# CE_BJTInfineonSOT343_v1.net
KiCad netlist of a schematic drawn in Altium Designer
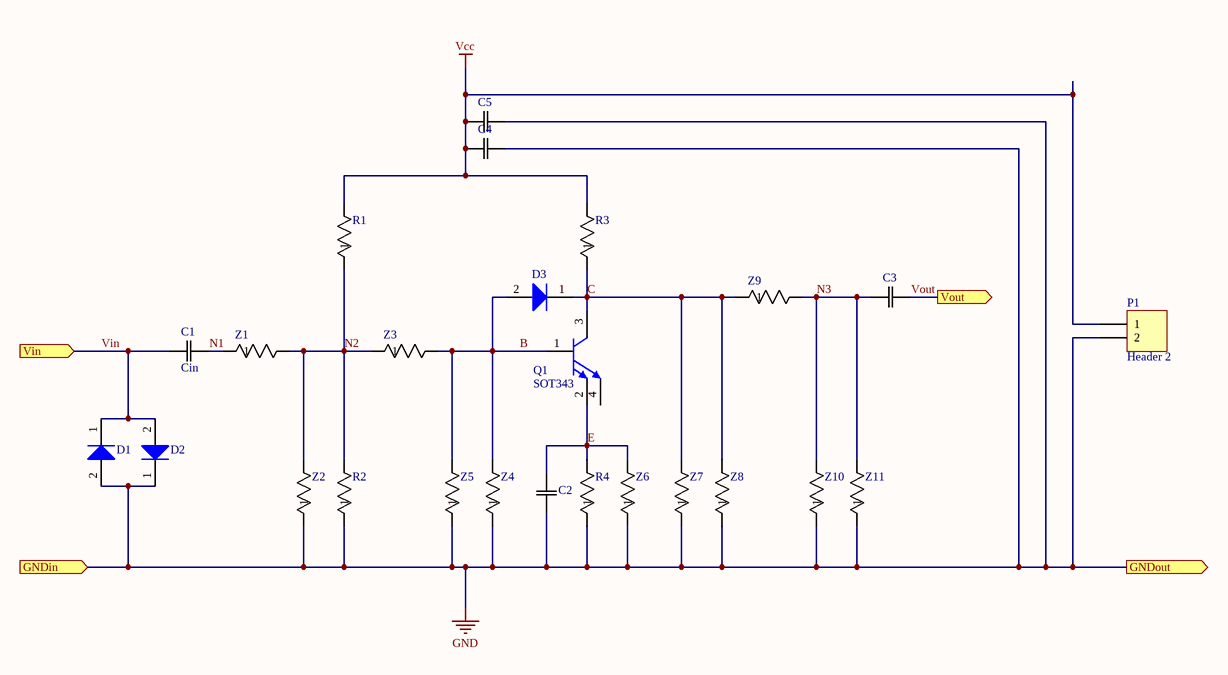
[diagram p0: CE_BJTInfineonSOT343_v1.SchDoc]

(export (version "E")
  (design (tool "Eeschema 10.0.6"))
  (components
    (comp (ref "C1")
      (value "Cin")
      (footprint "C0201")
      (description "No Description Available")
      (fields
        (field (name "MANUFACTURER_PART_NUMBER") "C0201C270J3GACTU")
        (field (name "COPYRIGHT") "Copyright (C) 2018 Accelerated Designs. All rights reserved")
      )
      (libsource (lib "0201Capacitor_Yageo") (part "C0201C270J3GACTU"))
    )
    (comp (ref "C2")
      (value "~")
      (footprint "C0201")
      (description "No Description Available")
      (fields
        (field (name "MANUFACTURER_PART_NUMBER") "C0201C270J3GACTU")
        (field (name "COPYRIGHT") "Copyright (C) 2018 Accelerated Designs. All rights reserved")
      )
      (libsource (lib "0201Capacitor_Yageo") (part "C0201C270J3GACTU"))
    )
    (comp (ref "C3")
      (value "~")
      (footprint "C0201")
      (description "No Description Available")
      (fields
        (field (name "MANUFACTURER_PART_NUMBER") "C0201C270J3GACTU")
        (field (name "COPYRIGHT") "Copyright (C) 2018 Accelerated Designs. All rights reserved")
      )
      (libsource (lib "0201Capacitor_Yageo") (part "C0201C270J3GACTU"))
    )
    (comp (ref "C4")
      (value "~")
      (footprint "CAP_CBR_0201")
      (description "No Description Available")
      (fields
        (field (name "MANUFACTURER_PART_NUMBER") "CBR02C399C3GAC")
        (field (name "COPYRIGHT") "Copyright (C) 2018 Accelerated Designs. All rights reserved")
      )
      (libsource (lib "0201Capacitor_KEMET") (part "CBR02C399C3GAC"))
    )
    (comp (ref "C5")
      (value "~")
      (footprint "CAP_CBR_0201")
      (description "No Description Available")
      (fields
        (field (name "MANUFACTURER_PART_NUMBER") "CBR02C399C3GAC")
        (field (name "COPYRIGHT") "Copyright (C) 2018 Accelerated Designs. All rights reserved")
      )
      (libsource (lib "0201Capacitor_KEMET") (part "CBR02C399C3GAC"))
    )
    (comp (ref "D1")
      (value "~")
      (footprint "INF-SOD323_V")
      (description "Single Silicon Schottky Diode, 110 mA IF Max, SOD32, Green")
      (fields (field (name "MANUFACTURER") "Infineon") (field (name "PARTNUMBER") "BAT15-03W"))
      (libsource (lib "Infineon_RFSchottkyDiode_SOD323") (part "BAT15-03W"))
    )
    (comp (ref "D2")
      (value "~")
      (footprint "INF-SOD323_V")
      (description "Single Silicon Schottky Diode, 110 mA IF Max, SOD32, Green")
      (fields (field (name "MANUFACTURER") "Infineon") (field (name "PARTNUMBER") "BAT15-03W"))
      (libsource (lib "Infineon_RFSchottkyDiode_SOD323") (part "BAT15-03W"))
    )
    (comp (ref "D3")
      (value "~")
      (footprint "INF-SOD323_V")
      (description "Single Silicon Schottky Diode, 110 mA IF Max, SOD32, Green")
      (fields (field (name "MANUFACTURER") "Infineon") (field (name "PARTNUMBER") "BAT15-03W"))
      (libsource (lib "Infineon_RFSchottkyDiode_SOD323") (part "BAT15-03W"))
    )
    (comp (ref "P1")
      (value "Header 2")
      (footprint "HDR1X2")
      (description "Header, 2-Pin")
      (fields (field (name "PUBLISHER") "Altium Limited"))
      (libsource (lib "Miscellaneous Connectors") (part "Header 2"))
    )
    (comp (ref "Q1")
      (value "SOT343")
      (footprint "INF-SOT343_V")
      (fields (field (name "MANUFACTURER") "Infineon") (field (name "PARTNUMBER") "BFP840ESD"))
      (libsource (lib "Infineon_RFBJT_SOT343") (part "BFP840ESD"))
    )
    (comp (ref "R1")
      (value "~")
      (footprint "RES_RC0201_P6XP3")
      (description "No Description Available")
      (fields
        (field (name "MANUFACTURER_PART_NUMBER") "RC0201FR-0718KL")
        (field (name "COPYRIGHT") "Copyright (C) 2018 Accelerated Designs. All rights reserved")
      )
      (libsource (lib "0201Resistor_Yageo") (part "RC0201FR-0718KL"))
    )
    (comp (ref "R2")
      (value "~")
      (footprint "RES_RC0201_P6XP3")
      (description "No Description Available")
      (fields
        (field (name "MANUFACTURER_PART_NUMBER") "RC0201FR-0718KL")
        (field (name "COPYRIGHT") "Copyright (C) 2018 Accelerated Designs. All rights reserved")
      )
      (libsource (lib "0201Resistor_Yageo") (part "RC0201FR-0718KL"))
    )
    (comp (ref "R3")
      (value "~")
      (footprint "RES_RC0201_P6XP3")
      (description "No Description Available")
      (fields
        (field (name "MANUFACTURER_PART_NUMBER") "RC0201FR-0718KL")
        (field (name "COPYRIGHT") "Copyright (C) 2018 Accelerated Designs. All rights reserved")
      )
      (libsource (lib "0201Resistor_Yageo") (part "RC0201FR-0718KL"))
    )
    (comp (ref "R4")
      (value "~")
      (footprint "RES_RC0201_P6XP3")
      (description "No Description Available")
      (fields
        (field (name "MANUFACTURER_PART_NUMBER") "RC0201FR-0718KL")
        (field (name "COPYRIGHT") "Copyright (C) 2018 Accelerated Designs. All rights reserved")
      )
      (libsource (lib "0201Resistor_Yageo") (part "RC0201FR-0718KL"))
    )
    (comp (ref "Z1")
      (value "~")
      (footprint "RES_RC0201_P6XP3")
      (description "No Description Available")
      (fields
        (field (name "MANUFACTURER_PART_NUMBER") "RC0201FR-0718KL")
        (field (name "COPYRIGHT") "Copyright (C) 2018 Accelerated Designs. All rights reserved")
      )
      (libsource (lib "0201Resistor_Yageo") (part "RC0201FR-0718KL"))
    )
    (comp (ref "Z2")
      (value "~")
      (footprint "RES_RC0201_P6XP3")
      (description "No Description Available")
      (fields
        (field (name "MANUFACTURER_PART_NUMBER") "RC0201FR-0718KL")
        (field (name "COPYRIGHT") "Copyright (C) 2018 Accelerated Designs. All rights reserved")
      )
      (libsource (lib "0201Resistor_Yageo") (part "RC0201FR-0718KL"))
    )
    (comp (ref "Z3")
      (value "~")
      (footprint "RES_RC0201_P6XP3")
      (description "No Description Available")
      (fields
        (field (name "MANUFACTURER_PART_NUMBER") "RC0201FR-0718KL")
        (field (name "COPYRIGHT") "Copyright (C) 2018 Accelerated Designs. All rights reserved")
      )
      (libsource (lib "0201Resistor_Yageo") (part "RC0201FR-0718KL"))
    )
    (comp (ref "Z4")
      (value "~")
      (footprint "RES_RC0201_P6XP3")
      (description "No Description Available")
      (fields
        (field (name "MANUFACTURER_PART_NUMBER") "RC0201FR-0718KL")
        (field (name "COPYRIGHT") "Copyright (C) 2018 Accelerated Designs. All rights reserved")
      )
      (libsource (lib "0201Resistor_Yageo") (part "RC0201FR-0718KL"))
    )
    (comp (ref "Z5")
      (value "~")
      (footprint "RES_RC0201_P6XP3")
      (description "No Description Available")
      (fields
        (field (name "MANUFACTURER_PART_NUMBER") "RC0201FR-0718KL")
        (field (name "COPYRIGHT") "Copyright (C) 2018 Accelerated Designs. All rights reserved")
      )
      (libsource (lib "0201Resistor_Yageo") (part "RC0201FR-0718KL"))
    )
    (comp (ref "Z6")
      (value "~")
      (footprint "RES_RC0201_P6XP3")
      (description "No Description Available")
      (fields
        (field (name "MANUFACTURER_PART_NUMBER") "RC0201FR-0718KL")
        (field (name "COPYRIGHT") "Copyright (C) 2018 Accelerated Designs. All rights reserved")
      )
      (libsource (lib "0201Resistor_Yageo") (part "RC0201FR-0718KL"))
    )
    (comp (ref "Z7")
      (value "~")
      (footprint "RES_RC0201_P6XP3")
      (description "No Description Available")
      (fields
        (field (name "MANUFACTURER_PART_NUMBER") "RC0201FR-0718KL")
        (field (name "COPYRIGHT") "Copyright (C) 2018 Accelerated Designs. All rights reserved")
      )
      (libsource (lib "0201Resistor_Yageo") (part "RC0201FR-0718KL"))
    )
    (comp (ref "Z8")
      (value "~")
      (footprint "RES_RC0201_P6XP3")
      (description "No Description Available")
      (fields
        (field (name "MANUFACTURER_PART_NUMBER") "RC0201FR-0718KL")
        (field (name "COPYRIGHT") "Copyright (C) 2018 Accelerated Designs. All rights reserved")
      )
      (libsource (lib "0201Resistor_Yageo") (part "RC0201FR-0718KL"))
    )
    (comp (ref "Z9")
      (value "~")
      (footprint "RES_RC0201_P6XP3")
      (description "No Description Available")
      (fields
        (field (name "MANUFACTURER_PART_NUMBER") "RC0201FR-0718KL")
        (field (name "COPYRIGHT") "Copyright (C) 2018 Accelerated Designs. All rights reserved")
      )
      (libsource (lib "0201Resistor_Yageo") (part "RC0201FR-0718KL"))
    )
    (comp (ref "Z10")
      (value "~")
      (footprint "RES_RC0201_P6XP3")
      (description "No Description Available")
      (fields
        (field (name "MANUFACTURER_PART_NUMBER") "RC0201FR-0718KL")
        (field (name "COPYRIGHT") "Copyright (C) 2018 Accelerated Designs. All rights reserved")
      )
      (libsource (lib "0201Resistor_Yageo") (part "RC0201FR-0718KL"))
    )
    (comp (ref "Z11")
      (value "~")
      (footprint "RES_RC0201_P6XP3")
      (description "No Description Available")
      (fields
        (field (name "MANUFACTURER_PART_NUMBER") "RC0201FR-0718KL")
        (field (name "COPYRIGHT") "Copyright (C) 2018 Accelerated Designs. All rights reserved")
      )
      (libsource (lib "0201Resistor_Yageo") (part "RC0201FR-0718KL"))
    )
  )
  (nets
    (net (code "1") (name "/B") (class "Default")
      (node (ref "D3") (pin "2") (pinfunction "A_2") (pintype "passive"))
      (node (ref "Q1") (pin "1") (pinfunction "B_1") (pintype "passive"))
      (node (ref "Z3") (pin "2") (pinfunction "2_2") (pintype "passive"))
      (node (ref "Z4") (pin "2") (pinfunction "2_2") (pintype "passive"))
      (node (ref "Z5") (pin "2") (pinfunction "2_2") (pintype "passive"))
    )
    (net (code "2") (name "/C") (class "Default")
      (node (ref "D3") (pin "1") (pinfunction "K_1") (pintype "passive"))
      (node (ref "Q1") (pin "3") (pinfunction "C_3") (pintype "passive"))
      (node (ref "R3") (pin "1") (pinfunction "1_1") (pintype "passive"))
      (node (ref "Z7") (pin "2") (pinfunction "2_2") (pintype "passive"))
      (node (ref "Z8") (pin "2") (pinfunction "2_2") (pintype "passive"))
      (node (ref "Z9") (pin "1") (pinfunction "1_1") (pintype "passive"))
    )
    (net (code "3") (name "/E") (class "Default")
      (node (ref "C2") (pin "2") (pinfunction "2_2") (pintype "passive"))
      (node (ref "Q1") (pin "2") (pinfunction "E_2") (pintype "passive"))
      (node (ref "R4") (pin "2") (pinfunction "2_2") (pintype "passive"))
      (node (ref "Z6") (pin "2") (pinfunction "2_2") (pintype "passive"))
    )
    (net (code "4") (name "/N1") (class "Default")
      (node (ref "C1") (pin "2") (pinfunction "2_2") (pintype "passive"))
      (node (ref "Z1") (pin "1") (pinfunction "1_1") (pintype "passive"))
    )
    (net (code "5") (name "/N2") (class "Default")
      (node (ref "R1") (pin "1") (pinfunction "1_1") (pintype "passive"))
      (node (ref "R2") (pin "2") (pinfunction "2_2") (pintype "passive"))
      (node (ref "Z1") (pin "2") (pinfunction "2_2") (pintype "passive"))
      (node (ref "Z2") (pin "2") (pinfunction "2_2") (pintype "passive"))
      (node (ref "Z3") (pin "1") (pinfunction "1_1") (pintype "passive"))
    )
    (net (code "6") (name "/N3") (class "Default")
      (node (ref "C3") (pin "1") (pinfunction "1_1") (pintype "passive"))
      (node (ref "Z10") (pin "2") (pinfunction "2_2") (pintype "passive"))
      (node (ref "Z11") (pin "2") (pinfunction "2_2") (pintype "passive"))
      (node (ref "Z9") (pin "2") (pinfunction "2_2") (pintype "passive"))
    )
    (net (code "7") (name "/Vin") (class "Default")
      (node (ref "C1") (pin "1") (pinfunction "1_1") (pintype "passive"))
      (node (ref "D1") (pin "1") (pinfunction "K_1") (pintype "passive"))
      (node (ref "D2") (pin "2") (pinfunction "A_2") (pintype "passive"))
    )
    (net (code "8") (name "/Vout") (class "Default")
      (node (ref "C3") (pin "2") (pinfunction "2_2") (pintype "passive"))
    )
    (net (code "9") (name "GND") (class "Default")
      (node (ref "C2") (pin "1") (pinfunction "1_1") (pintype "passive"))
      (node (ref "C4") (pin "2") (pinfunction "2_2") (pintype "passive"))
      (node (ref "C5") (pin "2") (pinfunction "2_2") (pintype "passive"))
      (node (ref "D1") (pin "2") (pinfunction "A_2") (pintype "passive"))
      (node (ref "D2") (pin "1") (pinfunction "K_1") (pintype "passive"))
      (node (ref "P1") (pin "2") (pinfunction "2_2") (pintype "passive"))
      (node (ref "R2") (pin "1") (pinfunction "1_1") (pintype "passive"))
      (node (ref "R4") (pin "1") (pinfunction "1_1") (pintype "passive"))
      (node (ref "Z10") (pin "1") (pinfunction "1_1") (pintype "passive"))
      (node (ref "Z11") (pin "1") (pinfunction "1_1") (pintype "passive"))
      (node (ref "Z2") (pin "1") (pinfunction "1_1") (pintype "passive"))
      (node (ref "Z4") (pin "1") (pinfunction "1_1") (pintype "passive"))
      (node (ref "Z5") (pin "1") (pinfunction "1_1") (pintype "passive"))
      (node (ref "Z6") (pin "1") (pinfunction "1_1") (pintype "passive"))
      (node (ref "Z7") (pin "1") (pinfunction "1_1") (pintype "passive"))
      (node (ref "Z8") (pin "1") (pinfunction "1_1") (pintype "passive"))
    )
    (net (code "10") (name "Vcc") (class "Default")
      (node (ref "C4") (pin "1") (pinfunction "1_1") (pintype "passive"))
      (node (ref "C5") (pin "1") (pinfunction "1_1") (pintype "passive"))
      (node (ref "P1") (pin "1") (pinfunction "1_1") (pintype "passive"))
      (node (ref "R1") (pin "2") (pinfunction "2_2") (pintype "passive"))
      (node (ref "R3") (pin "2") (pinfunction "2_2") (pintype "passive"))
    )
    (net (code "11") (name "unconnected-(Q1-E-Pad4)") (class "Default")
      (node (ref "Q1") (pin "4") (pinfunction "E_4") (pintype "passive"))
    )
  )
)
